# Shield_PCB.net
KiCad netlist of a schematic drawn in Altium Designer
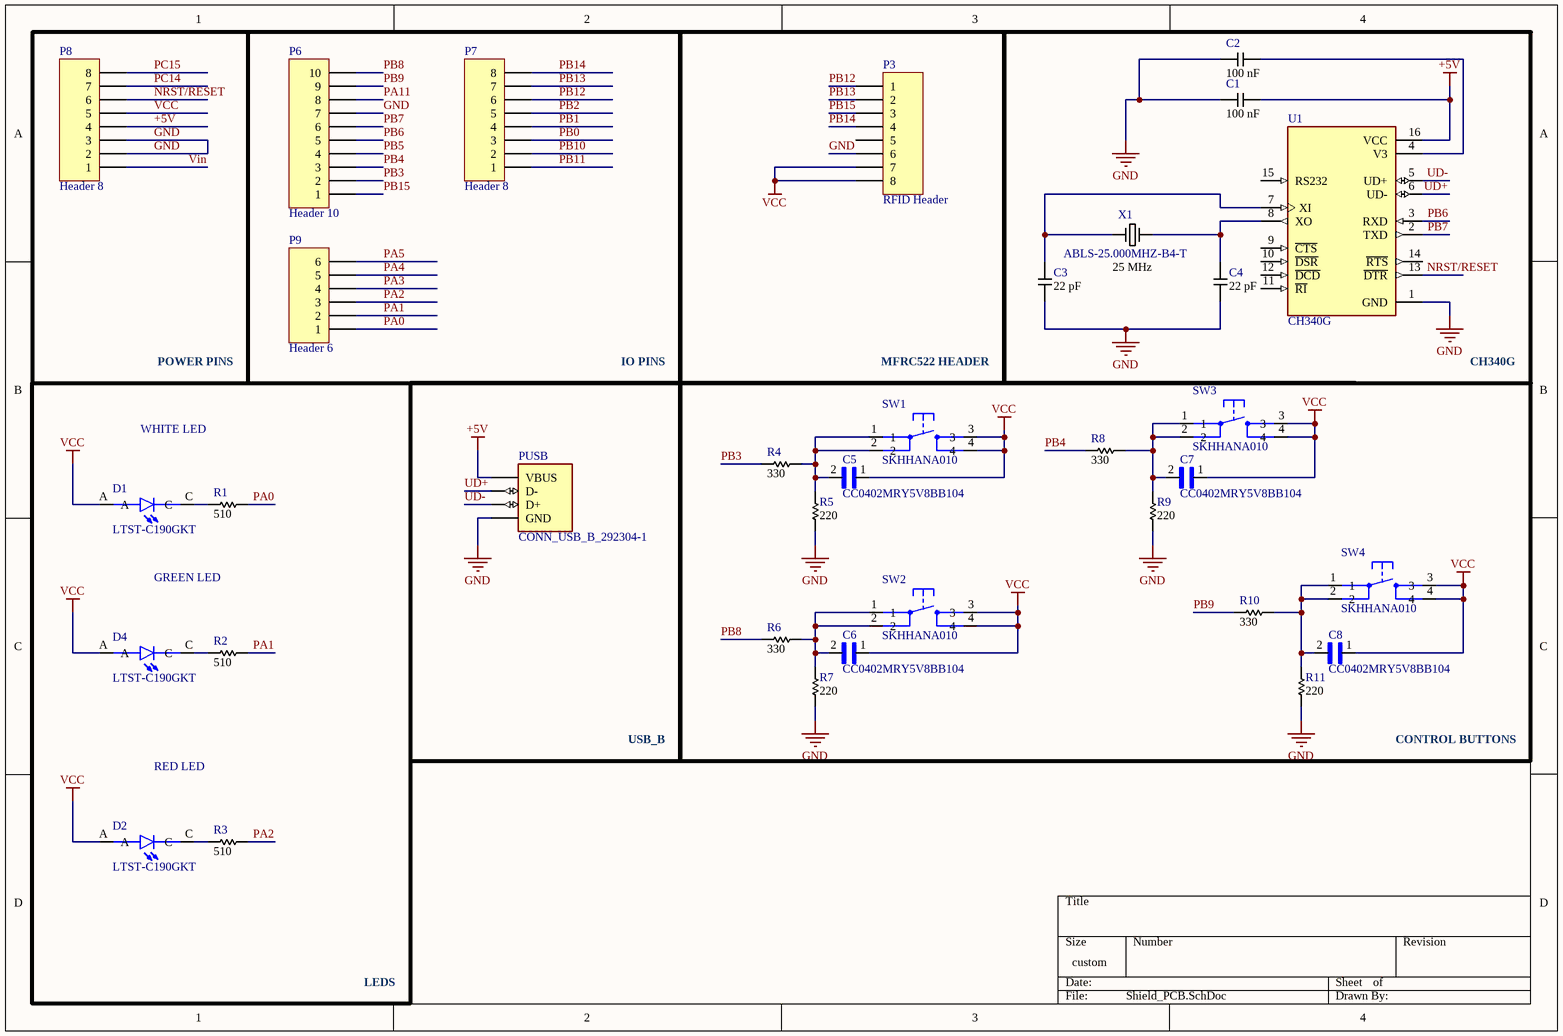
[diagram p0: Shield_PCB.SchDoc]

(export (version "E")
  (design (tool "Eeschema 10.0.6"))
  (components
    (comp (ref "C1")
      (value "CL10B222KB8NNNC")
      (footprint "SAMSUNG_CAP_0603_090")
      (description "CAP CER 2200PF 50V X7R 0603")
      (fields
        (field (name "CAPACITANCE") "100 nF")
        (field (name "MANUFACTURER") "Samsung Electro-Mechanics")
        (field (name "TOLERANCE") "±10%")
      )
      (libsource (lib "Library") (part "CL10B222KB8NNNC"))
    )
    (comp (ref "C2")
      (value "CL10B222KB8NNNC")
      (footprint "SAMSUNG_CAP_0603_090")
      (description "CAP CER 2200PF 50V X7R 0603")
      (fields
        (field (name "CAPACITANCE") "100 nF")
        (field (name "MANUFACTURER") "Samsung Electro-Mechanics")
        (field (name "TOLERANCE") "±10%")
      )
      (libsource (lib "Library") (part "CL10B222KB8NNNC"))
    )
    (comp (ref "C3")
      (value "CL10B222KB8NNNC")
      (footprint "SAMSUNG_CAP_0603_090")
      (description "CAP CER 2200PF 50V X7R 0603")
      (fields
        (field (name "CAPACITANCE") "22 pF")
        (field (name "MANUFACTURER") "Samsung Electro-Mechanics")
        (field (name "TOLERANCE") "±10%")
      )
      (libsource (lib "Library") (part "CL10B222KB8NNNC"))
    )
    (comp (ref "C4")
      (value "CL10B222KB8NNNC")
      (footprint "SAMSUNG_CAP_0603_090")
      (description "CAP CER 2200PF 50V X7R 0603")
      (fields
        (field (name "CAPACITANCE") "22 pF")
        (field (name "MANUFACTURER") "Samsung Electro-Mechanics")
        (field (name "TOLERANCE") "±10%")
      )
      (libsource (lib "Library") (part "CL10B222KB8NNNC"))
    )
    (comp (ref "C5")
      (value "CC0402MRY5V8BB104")
      (footprint "CAPC1005X55N")
      (description "CAP CER 0.1UF 25V Y5V 0402")
      (libsource (lib "CC0402MRY5V8BB104") (part "CC0402MRY5V8BB104"))
    )
    (comp (ref "C6")
      (value "CC0402MRY5V8BB104")
      (footprint "CAPC1005X55N")
      (description "CAP CER 0.1UF 25V Y5V 0402")
      (libsource (lib "CC0402MRY5V8BB104") (part "CC0402MRY5V8BB104"))
    )
    (comp (ref "C7")
      (value "CC0402MRY5V8BB104")
      (footprint "CAPC1005X55N")
      (description "CAP CER 0.1UF 25V Y5V 0402")
      (libsource (lib "CC0402MRY5V8BB104") (part "CC0402MRY5V8BB104"))
    )
    (comp (ref "C8")
      (value "CC0402MRY5V8BB104")
      (footprint "CAPC1005X55N")
      (description "CAP CER 0.1UF 25V Y5V 0402")
      (libsource (lib "CC0402MRY5V8BB104") (part "CC0402MRY5V8BB104"))
    )
    (comp (ref "D1")
      (value "LTST-C190GKT")
      (footprint "LEDM1608X80")
      (description "Green 569nm LED Indication - Discrete 2.1V 0603 (1608 Metric)")
      (fields (field (name "MF") "Lite-On Inc.") (field (name "DIGI-KEY_PART_NUMBER") "160-1183-1-ND"))
      (libsource (lib "LTST-C190GKT") (part "LTST-C190GKT"))
    )
    (comp (ref "D2")
      (value "LTST-C190GKT")
      (footprint "LEDM1608X80")
      (description "Green 569nm LED Indication - Discrete 2.1V 0603 (1608 Metric)")
      (fields (field (name "MF") "Lite-On Inc.") (field (name "DIGI-KEY_PART_NUMBER") "160-1183-1-ND"))
      (libsource (lib "LTST-C190GKT") (part "LTST-C190GKT"))
    )
    (comp (ref "D4")
      (value "LTST-C190GKT")
      (footprint "LEDM1608X80")
      (description "Green 569nm LED Indication - Discrete 2.1V 0603 (1608 Metric)")
      (fields (field (name "MF") "Lite-On Inc.") (field (name "DIGI-KEY_PART_NUMBER") "160-1183-1-ND"))
      (libsource (lib "LTST-C190GKT") (part "LTST-C190GKT"))
    )
    (comp (ref "P3")
      (value "RFID Header")
      (footprint "HDR1X8")
      (description "Header, 8-Pin")
      (fields (field (name "PUBLISHER") "Altium Limited"))
      (libsource (lib "Miscellaneous Connectors") (part "Header 8"))
    )
    (comp (ref "P6")
      (value "Header 10")
      (footprint "HDR1X10")
      (description "Header, 10-Pin")
      (fields (field (name "PUBLISHER") "Altium Limited"))
      (libsource (lib "Miscellaneous Connectors") (part "Header 10"))
    )
    (comp (ref "P7")
      (value "Header 8")
      (footprint "HDR1X8")
      (description "Header, 8-Pin")
      (fields (field (name "PUBLISHER") "Altium Limited"))
      (libsource (lib "") (part "Header 8_1"))
    )
    (comp (ref "P8")
      (value "Header 8")
      (footprint "HDR1X8")
      (description "Header, 8-Pin")
      (fields (field (name "PUBLISHER") "Altium Limited"))
      (libsource (lib "") (part "Header 8_1"))
    )
    (comp (ref "P9")
      (value "Header 6")
      (footprint "HDR1X6")
      (description "Header, 6-Pin")
      (fields (field (name "PUBLISHER") "Altium Limited"))
      (libsource (lib "Miscellaneous Connectors") (part "Header 6"))
    )
    (comp (ref "PUSB")
      (value "CONN_USB_B_292304-1")
      (footprint "TE_292304-1")
      (description "USB-B _USB TYPE-B_ USB 2.0 Receptacle Connector 4 Position Through Hole, Right Angle")
      (fields (field (name "MF") "TE Connectivity") (field (name "MP") "292304-1"))
      (libsource (lib "292304-1") (part "292304-1"))
    )
    (comp (ref "R1")
      (value "0603SAJ0331T5E")
      (footprint "ROYALOHM_RES_0603")
      (description "RES SMD 510R OHM 5% 1/10W 0603")
      (fields
        (field (name "RESISTANCE") "510")
        (field (name "MANUFACTURER") "Royalohm")
        (field (name "TOLERANCE") "±5%")
      )
      (libsource (lib "Library") (part "0603SAJ0331T5E"))
    )
    (comp (ref "R2")
      (value "0603SAJ0331T5E")
      (footprint "ROYALOHM_RES_0603")
      (description "RES SMD 510R OHM 5% 1/10W 0603")
      (fields
        (field (name "RESISTANCE") "510")
        (field (name "MANUFACTURER") "Royalohm")
        (field (name "TOLERANCE") "±5%")
      )
      (libsource (lib "Library") (part "0603SAJ0331T5E"))
    )
    (comp (ref "R3")
      (value "0603SAJ0331T5E")
      (footprint "ROYALOHM_RES_0603")
      (description "RES SMD 510R OHM 5% 1/10W 0603")
      (fields
        (field (name "RESISTANCE") "510")
        (field (name "MANUFACTURER") "Royalohm")
        (field (name "TOLERANCE") "±5%")
      )
      (libsource (lib "Library") (part "0603SAJ0331T5E"))
    )
    (comp (ref "R4")
      (value "0603SAJ0331T5E")
      (footprint "ROYALOHM_RES_0603")
      (description "RES SMD 510R OHM 5% 1/10W 0603")
      (fields
        (field (name "RESISTANCE") "330")
        (field (name "MANUFACTURER") "Royalohm")
        (field (name "TOLERANCE") "±5%")
      )
      (libsource (lib "Library") (part "0603SAJ0331T5E"))
    )
    (comp (ref "R5")
      (value "0603SAJ0331T5E")
      (footprint "ROYALOHM_RES_0603")
      (description "RES SMD 510R OHM 5% 1/10W 0603")
      (fields
        (field (name "RESISTANCE") "220")
        (field (name "MANUFACTURER") "Royalohm")
        (field (name "TOLERANCE") "±5%")
      )
      (libsource (lib "Library") (part "0603SAJ0331T5E"))
    )
    (comp (ref "R6")
      (value "0603SAJ0331T5E")
      (footprint "ROYALOHM_RES_0603")
      (description "RES SMD 510R OHM 5% 1/10W 0603")
      (fields
        (field (name "RESISTANCE") "330")
        (field (name "MANUFACTURER") "Royalohm")
        (field (name "TOLERANCE") "±5%")
      )
      (libsource (lib "Library") (part "0603SAJ0331T5E"))
    )
    (comp (ref "R7")
      (value "0603SAJ0331T5E")
      (footprint "ROYALOHM_RES_0603")
      (description "RES SMD 510R OHM 5% 1/10W 0603")
      (fields
        (field (name "RESISTANCE") "220")
        (field (name "MANUFACTURER") "Royalohm")
        (field (name "TOLERANCE") "±5%")
      )
      (libsource (lib "Library") (part "0603SAJ0331T5E"))
    )
    (comp (ref "R8")
      (value "0603SAJ0331T5E")
      (footprint "ROYALOHM_RES_0603")
      (description "RES SMD 510R OHM 5% 1/10W 0603")
      (fields
        (field (name "RESISTANCE") "330")
        (field (name "MANUFACTURER") "Royalohm")
        (field (name "TOLERANCE") "±5%")
      )
      (libsource (lib "Library") (part "0603SAJ0331T5E"))
    )
    (comp (ref "R9")
      (value "0603SAJ0331T5E")
      (footprint "ROYALOHM_RES_0603")
      (description "RES SMD 510R OHM 5% 1/10W 0603")
      (fields
        (field (name "RESISTANCE") "220")
        (field (name "MANUFACTURER") "Royalohm")
        (field (name "TOLERANCE") "±5%")
      )
      (libsource (lib "Library") (part "0603SAJ0331T5E"))
    )
    (comp (ref "R10")
      (value "0603SAJ0331T5E")
      (footprint "ROYALOHM_RES_0603")
      (description "RES SMD 510R OHM 5% 1/10W 0603")
      (fields
        (field (name "RESISTANCE") "330")
        (field (name "MANUFACTURER") "Royalohm")
        (field (name "TOLERANCE") "±5%")
      )
      (libsource (lib "Library") (part "0603SAJ0331T5E"))
    )
    (comp (ref "R11")
      (value "0603SAJ0331T5E")
      (footprint "ROYALOHM_RES_0603")
      (description "RES SMD 510R OHM 5% 1/10W 0603")
      (fields
        (field (name "RESISTANCE") "220")
        (field (name "MANUFACTURER") "Royalohm")
        (field (name "TOLERANCE") "±5%")
      )
      (libsource (lib "Library") (part "0603SAJ0331T5E"))
    )
    (comp (ref "SW1")
      (value "SKHHANA010")
      (footprint "SW_SKHHANA010")
      (description "Switch Tactile N.O. SPST Round Button PC Pins 0.05A 12VDC 0.98N Thru-Hole Bulk")
      (fields (field (name "MF") "ALPS"))
      (libsource (lib "SKHHANA010") (part "SKHHANA010"))
    )
    (comp (ref "SW2")
      (value "SKHHANA010")
      (footprint "SW_SKHHANA010")
      (description "Switch Tactile N.O. SPST Round Button PC Pins 0.05A 12VDC 0.98N Thru-Hole Bulk")
      (fields (field (name "MF") "ALPS"))
      (libsource (lib "SKHHANA010") (part "SKHHANA010"))
    )
    (comp (ref "SW3")
      (value "SKHHANA010")
      (footprint "SW_SKHHANA010")
      (description "Switch Tactile N.O. SPST Round Button PC Pins 0.05A 12VDC 0.98N Thru-Hole Bulk")
      (fields (field (name "MF") "ALPS"))
      (libsource (lib "SKHHANA010") (part "SKHHANA010"))
    )
    (comp (ref "SW4")
      (value "SKHHANA010")
      (footprint "SW_SKHHANA010")
      (description "Switch Tactile N.O. SPST Round Button PC Pins 0.05A 12VDC 0.98N Thru-Hole Bulk")
      (fields (field (name "MF") "ALPS"))
      (libsource (lib "SKHHANA010") (part "SKHHANA010"))
    )
    (comp (ref "U1")
      (value "CH340G")
      (footprint "SOIC127P600X180-16N")
      (description "USB Interface Integrated Circuit")
      (fields (field (name "MP") "Ch340G") (field (name "MF") "WCH"))
      (libsource (lib "CH340G") (part "CH340G"))
    )
    (comp (ref "X1")
      (value "ABLS-25.000MHZ-B4-T")
      (footprint "ABRACON_HC-49/US")
      (description "CRYSTAL 8.0000MHZ 18PF SMD")
      (fields
        (field (name "FREQUENCY") "25 MHz")
        (field (name "PART NUMBER") "ABLS-8.000MHZ-B4-T")
        (field (name "MANUFACTURER") "Abracon LLC")
      )
      (libsource (lib "Library") (part "ABLS-8.000MHZ-B4-T"))
    )
  )
  (nets
    (net (code "1") (name "+5V") (class "Default")
      (node (ref "C1") (pin "2") (pinfunction "2_2") (pintype "passive"))
      (node (ref "P8") (pin "4") (pinfunction "4_4") (pintype "passive"))
      (node (ref "PUSB") (pin "1") (pinfunction "VBUS_1") (pintype "power_in"))
      (node (ref "U1") (pin "16") (pinfunction "VCC_16") (pintype "power_in"))
    )
    (net (code "2") (name "/NRST{slash}RESET") (class "Default")
      (node (ref "P8") (pin "6") (pinfunction "6_6") (pintype "passive"))
      (node (ref "U1") (pin "13") (pinfunction "~{DTR}_13") (pintype "output"))
    )
    (net (code "3") (name "/PA0") (class "Default")
      (node (ref "P9") (pin "1") (pinfunction "1_1") (pintype "passive"))
      (node (ref "R1") (pin "2") (pinfunction "2_2") (pintype "passive"))
    )
    (net (code "4") (name "/PA1") (class "Default")
      (node (ref "P9") (pin "2") (pinfunction "2_2") (pintype "passive"))
      (node (ref "R2") (pin "2") (pinfunction "2_2") (pintype "passive"))
    )
    (net (code "5") (name "/PA2") (class "Default")
      (node (ref "P9") (pin "3") (pinfunction "3_3") (pintype "passive"))
      (node (ref "R3") (pin "2") (pinfunction "2_2") (pintype "passive"))
    )
    (net (code "6") (name "/PA3") (class "Default")
      (node (ref "P9") (pin "4") (pinfunction "4_4") (pintype "passive"))
    )
    (net (code "7") (name "/PA4") (class "Default")
      (node (ref "P9") (pin "5") (pinfunction "5_5") (pintype "passive"))
    )
    (net (code "8") (name "/PA5") (class "Default")
      (node (ref "P9") (pin "6") (pinfunction "6_6") (pintype "passive"))
    )
    (net (code "9") (name "/PA11") (class "Default")
      (node (ref "P6") (pin "8") (pinfunction "8_8") (pintype "passive"))
    )
    (net (code "10") (name "/PB0") (class "Default")
      (node (ref "P7") (pin "3") (pinfunction "3_3") (pintype "passive"))
    )
    (net (code "11") (name "/PB1") (class "Default")
      (node (ref "P7") (pin "4") (pinfunction "4_4") (pintype "passive"))
    )
    (net (code "12") (name "/PB2") (class "Default")
      (node (ref "P7") (pin "5") (pinfunction "5_5") (pintype "passive"))
    )
    (net (code "13") (name "/PB3") (class "Default")
      (node (ref "P6") (pin "2") (pinfunction "2_2") (pintype "passive"))
      (node (ref "R4") (pin "1") (pinfunction "1_1") (pintype "passive"))
    )
    (net (code "14") (name "/PB4") (class "Default")
      (node (ref "P6") (pin "3") (pinfunction "3_3") (pintype "passive"))
      (node (ref "R8") (pin "1") (pinfunction "1_1") (pintype "passive"))
    )
    (net (code "15") (name "/PB5") (class "Default")
      (node (ref "P6") (pin "4") (pinfunction "4_4") (pintype "passive"))
    )
    (net (code "16") (name "/PB6") (class "Default")
      (node (ref "P6") (pin "5") (pinfunction "5_5") (pintype "passive"))
      (node (ref "U1") (pin "3") (pinfunction "RXD_3") (pintype "input"))
    )
    (net (code "17") (name "/PB7") (class "Default")
      (node (ref "P6") (pin "6") (pinfunction "6_6") (pintype "passive"))
      (node (ref "U1") (pin "2") (pinfunction "TXD_2") (pintype "output"))
    )
    (net (code "18") (name "/PB8") (class "Default")
      (node (ref "P6") (pin "10") (pinfunction "10_10") (pintype "passive"))
      (node (ref "R6") (pin "1") (pinfunction "1_1") (pintype "passive"))
    )
    (net (code "19") (name "/PB9") (class "Default")
      (node (ref "P6") (pin "9") (pinfunction "9_9") (pintype "passive"))
      (node (ref "R10") (pin "1") (pinfunction "1_1") (pintype "passive"))
    )
    (net (code "20") (name "/PB10") (class "Default")
      (node (ref "P7") (pin "2") (pinfunction "2_2") (pintype "passive"))
    )
    (net (code "21") (name "/PB11") (class "Default")
      (node (ref "P7") (pin "1") (pinfunction "1_1") (pintype "passive"))
    )
    (net (code "22") (name "/PB12") (class "Default")
      (node (ref "P3") (pin "1") (pinfunction "1_1") (pintype "passive"))
      (node (ref "P7") (pin "6") (pinfunction "6_6") (pintype "passive"))
    )
    (net (code "23") (name "/PB13") (class "Default")
      (node (ref "P3") (pin "2") (pinfunction "2_2") (pintype "passive"))
      (node (ref "P7") (pin "7") (pinfunction "7_7") (pintype "passive"))
    )
    (net (code "24") (name "/PB14") (class "Default")
      (node (ref "P3") (pin "4") (pinfunction "4_4") (pintype "passive"))
      (node (ref "P7") (pin "8") (pinfunction "8_8") (pintype "passive"))
    )
    (net (code "25") (name "/PB15") (class "Default")
      (node (ref "P3") (pin "3") (pinfunction "3_3") (pintype "passive"))
      (node (ref "P6") (pin "1") (pinfunction "1_1") (pintype "passive"))
    )
    (net (code "26") (name "/PC14") (class "Default")
      (node (ref "P8") (pin "7") (pinfunction "7_7") (pintype "passive"))
    )
    (net (code "27") (name "/PC15") (class "Default")
      (node (ref "P8") (pin "8") (pinfunction "8_8") (pintype "passive"))
    )
    (net (code "28") (name "/UD+") (class "Default")
      (node (ref "PUSB") (pin "2") (pinfunction "D-_2") (pintype "bidirectional"))
      (node (ref "U1") (pin "6") (pinfunction "UD-_6") (pintype "bidirectional"))
    )
    (net (code "29") (name "/UD-") (class "Default")
      (node (ref "PUSB") (pin "3") (pinfunction "D+_3") (pintype "bidirectional"))
      (node (ref "U1") (pin "5") (pinfunction "UD+_5") (pintype "bidirectional"))
    )
    (net (code "30") (name "/Vin") (class "Default")
      (node (ref "P8") (pin "1") (pinfunction "1_1") (pintype "passive"))
    )
    (net (code "31") (name "GND") (class "Default")
      (node (ref "C1") (pin "1") (pinfunction "1_1") (pintype "passive"))
      (node (ref "C2") (pin "1") (pinfunction "1_1") (pintype "passive"))
      (node (ref "C3") (pin "1") (pinfunction "1_1") (pintype "passive"))
      (node (ref "C4") (pin "1") (pinfunction "1_1") (pintype "passive"))
      (node (ref "P3") (pin "6") (pinfunction "6_6") (pintype "passive"))
      (node (ref "P6") (pin "7") (pinfunction "7_7") (pintype "passive"))
      (node (ref "P8") (pin "2") (pinfunction "2_2") (pintype "passive"))
      (node (ref "P8") (pin "3") (pinfunction "3_3") (pintype "passive"))
      (node (ref "PUSB") (pin "4") (pinfunction "GND_4") (pintype "power_in"))
      (node (ref "R11") (pin "1") (pinfunction "1_1") (pintype "passive"))
      (node (ref "R5") (pin "1") (pinfunction "1_1") (pintype "passive"))
      (node (ref "R7") (pin "1") (pinfunction "1_1") (pintype "passive"))
      (node (ref "R9") (pin "1") (pinfunction "1_1") (pintype "passive"))
      (node (ref "U1") (pin "1") (pinfunction "GND_1") (pintype "power_in"))
    )
    (net (code "32") (name "Net-(C5-Pad2)") (class "Default")
      (node (ref "C5") (pin "2") (pinfunction "2_2") (pintype "passive"))
      (node (ref "R4") (pin "2") (pinfunction "2_2") (pintype "passive"))
      (node (ref "R5") (pin "2") (pinfunction "2_2") (pintype "passive"))
      (node (ref "SW1") (pin "1") (pinfunction "1_1") (pintype "passive"))
      (node (ref "SW1") (pin "2") (pinfunction "2_2") (pintype "passive"))
    )
    (net (code "33") (name "Net-(C6-Pad2)") (class "Default")
      (node (ref "C6") (pin "2") (pinfunction "2_2") (pintype "passive"))
      (node (ref "R6") (pin "2") (pinfunction "2_2") (pintype "passive"))
      (node (ref "R7") (pin "2") (pinfunction "2_2") (pintype "passive"))
      (node (ref "SW2") (pin "1") (pinfunction "1_1") (pintype "passive"))
      (node (ref "SW2") (pin "2") (pinfunction "2_2") (pintype "passive"))
    )
    (net (code "34") (name "Net-(C7-Pad2)") (class "Default")
      (node (ref "C7") (pin "2") (pinfunction "2_2") (pintype "passive"))
      (node (ref "R8") (pin "2") (pinfunction "2_2") (pintype "passive"))
      (node (ref "R9") (pin "2") (pinfunction "2_2") (pintype "passive"))
      (node (ref "SW3") (pin "1") (pinfunction "1_1") (pintype "passive"))
      (node (ref "SW3") (pin "2") (pinfunction "2_2") (pintype "passive"))
    )
    (net (code "35") (name "Net-(C8-Pad2)") (class "Default")
      (node (ref "C8") (pin "2") (pinfunction "2_2") (pintype "passive"))
      (node (ref "R10") (pin "2") (pinfunction "2_2") (pintype "passive"))
      (node (ref "R11") (pin "2") (pinfunction "2_2") (pintype "passive"))
      (node (ref "SW4") (pin "1") (pinfunction "1_1") (pintype "passive"))
      (node (ref "SW4") (pin "2") (pinfunction "2_2") (pintype "passive"))
    )
    (net (code "36") (name "Net-(D1-PadC)") (class "Default")
      (node (ref "D1") (pin "C") (pinfunction "C_C") (pintype "passive"))
      (node (ref "R1") (pin "1") (pinfunction "1_1") (pintype "passive"))
    )
    (net (code "37") (name "Net-(D2-PadC)") (class "Default")
      (node (ref "D2") (pin "C") (pinfunction "C_C") (pintype "passive"))
      (node (ref "R3") (pin "1") (pinfunction "1_1") (pintype "passive"))
    )
    (net (code "38") (name "Net-(D4-PadC)") (class "Default")
      (node (ref "D4") (pin "C") (pinfunction "C_C") (pintype "passive"))
      (node (ref "R2") (pin "1") (pinfunction "1_1") (pintype "passive"))
    )
    (net (code "39") (name "Net-(U1-V3)") (class "Default")
      (node (ref "C2") (pin "2") (pinfunction "2_2") (pintype "passive"))
      (node (ref "U1") (pin "4") (pinfunction "V3_4") (pintype "power_in"))
    )
    (net (code "40") (name "Net-(U1-XI)") (class "Default")
      (node (ref "C3") (pin "2") (pinfunction "2_2") (pintype "passive"))
      (node (ref "U1") (pin "7") (pinfunction "XI_7") (pintype "input"))
      (node (ref "X1") (pin "1") (pinfunction "1_1") (pintype "passive"))
    )
    (net (code "41") (name "Net-(U1-XO)") (class "Default")
      (node (ref "C4") (pin "2") (pinfunction "2_2") (pintype "passive"))
      (node (ref "U1") (pin "8") (pinfunction "XO_8") (pintype "output"))
      (node (ref "X1") (pin "2") (pinfunction "2_2") (pintype "passive"))
    )
    (net (code "42") (name "VCC") (class "Default")
      (node (ref "C5") (pin "1") (pinfunction "1_1") (pintype "passive"))
      (node (ref "C6") (pin "1") (pinfunction "1_1") (pintype "passive"))
      (node (ref "C7") (pin "1") (pinfunction "1_1") (pintype "passive"))
      (node (ref "C8") (pin "1") (pinfunction "1_1") (pintype "passive"))
      (node (ref "D1") (pin "A") (pinfunction "A_A") (pintype "passive"))
      (node (ref "D2") (pin "A") (pinfunction "A_A") (pintype "passive"))
      (node (ref "D4") (pin "A") (pinfunction "A_A") (pintype "passive"))
      (node (ref "P3") (pin "7") (pinfunction "7_7") (pintype "passive"))
      (node (ref "P3") (pin "8") (pinfunction "8_8") (pintype "passive"))
      (node (ref "P8") (pin "5") (pinfunction "5_5") (pintype "passive"))
      (node (ref "SW1") (pin "3") (pinfunction "3_3") (pintype "passive"))
      (node (ref "SW1") (pin "4") (pinfunction "4_4") (pintype "passive"))
      (node (ref "SW2") (pin "3") (pinfunction "3_3") (pintype "passive"))
      (node (ref "SW2") (pin "4") (pinfunction "4_4") (pintype "passive"))
      (node (ref "SW3") (pin "3") (pinfunction "3_3") (pintype "passive"))
      (node (ref "SW3") (pin "4") (pinfunction "4_4") (pintype "passive"))
      (node (ref "SW4") (pin "3") (pinfunction "3_3") (pintype "passive"))
      (node (ref "SW4") (pin "4") (pinfunction "4_4") (pintype "passive"))
    )
    (net (code "43") (name "unconnected-(P3-Pad5)") (class "Default")
      (node (ref "P3") (pin "5") (pinfunction "5_5") (pintype "passive"))
    )
    (net (code "44") (name "unconnected-(U1-RS232-Pad15)") (class "Default")
      (node (ref "U1") (pin "15") (pinfunction "RS232_15") (pintype "input"))
    )
    (net (code "45") (name "unconnected-(U1-~{CTS}-Pad9)") (class "Default")
      (node (ref "U1") (pin "9") (pinfunction "~{CTS}_9") (pintype "input"))
    )
    (net (code "46") (name "unconnected-(U1-~{DCD}-Pad12)") (class "Default")
      (node (ref "U1") (pin "12") (pinfunction "~{DCD}_12") (pintype "input"))
    )
    (net (code "47") (name "unconnected-(U1-~{DSR}-Pad10)") (class "Default")
      (node (ref "U1") (pin "10") (pinfunction "~{DSR}_10") (pintype "input"))
    )
    (net (code "48") (name "unconnected-(U1-~{RI}-Pad11)") (class "Default")
      (node (ref "U1") (pin "11") (pinfunction "~{RI}_11") (pintype "input"))
    )
    (net (code "49") (name "unconnected-(U1-~{RTS}-Pad14)") (class "Default")
      (node (ref "U1") (pin "14") (pinfunction "~{RTS}_14") (pintype "output"))
    )
  )
)
